# HVP_ADC_CONNECTIONS.net
KiCad netlist of a schematic drawn in Altium Designer
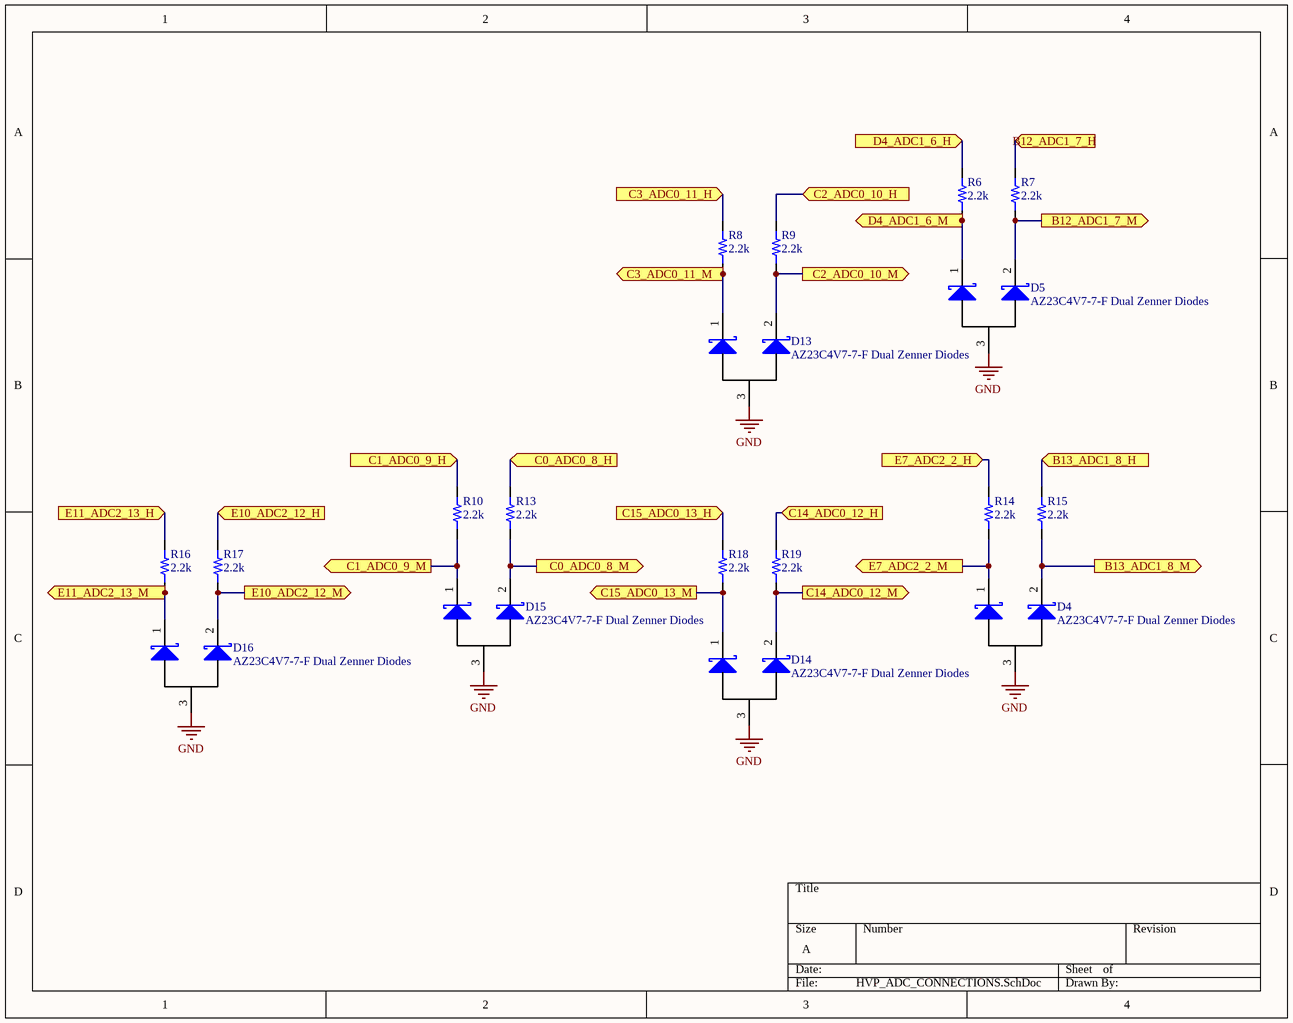
[diagram p0: HVP_ADC_CONNECTIONS.SchDoc]

(export (version "E")
  (design (tool "Eeschema 10.0.6"))
  (components
    (comp (ref "D4")
      (value "AZ23C4V7-7-F Dual Zenner Diodes")
      (footprint "SOT23-3")
      (description "DIODE ZENER ARRAY 4.7V SOT23-3")
      (fields
        (field (name "POWER") "300mW")
        (field (name "MFRPARTNO") "AZ23C4V7-7-F")
        (field (name "CREATED_BY") "Angel Delgado")
      )
      (libsource (lib "Altium-Lib") (part "AZ23C4V7-7-F Dual Zenner Diodes"))
    )
    (comp (ref "D5")
      (value "AZ23C4V7-7-F Dual Zenner Diodes")
      (footprint "SOT23-3")
      (description "DIODE ZENER ARRAY 4.7V SOT23-3")
      (fields
        (field (name "POWER") "300mW")
        (field (name "MFRPARTNO") "AZ23C4V7-7-F")
        (field (name "CREATED_BY") "Angel Delgado")
      )
      (libsource (lib "Altium-Lib") (part "AZ23C4V7-7-F Dual Zenner Diodes"))
    )
    (comp (ref "D13")
      (value "AZ23C4V7-7-F Dual Zenner Diodes")
      (footprint "SOT23-3")
      (description "DIODE ZENER ARRAY 4.7V SOT23-3")
      (fields
        (field (name "POWER") "300mW")
        (field (name "MFRPARTNO") "AZ23C4V7-7-F")
        (field (name "CREATED_BY") "Angel Delgado")
      )
      (libsource (lib "Altium-Lib") (part "AZ23C4V7-7-F Dual Zenner Diodes"))
    )
    (comp (ref "D14")
      (value "AZ23C4V7-7-F Dual Zenner Diodes")
      (footprint "SOT23-3")
      (description "DIODE ZENER ARRAY 4.7V SOT23-3")
      (fields
        (field (name "POWER") "300mW")
        (field (name "MFRPARTNO") "AZ23C4V7-7-F")
        (field (name "CREATED_BY") "Angel Delgado")
      )
      (libsource (lib "Altium-Lib") (part "AZ23C4V7-7-F Dual Zenner Diodes"))
    )
    (comp (ref "D15")
      (value "AZ23C4V7-7-F Dual Zenner Diodes")
      (footprint "SOT23-3")
      (description "DIODE ZENER ARRAY 4.7V SOT23-3")
      (fields
        (field (name "POWER") "300mW")
        (field (name "MFRPARTNO") "AZ23C4V7-7-F")
        (field (name "CREATED_BY") "Angel Delgado")
      )
      (libsource (lib "Altium-Lib") (part "AZ23C4V7-7-F Dual Zenner Diodes"))
    )
    (comp (ref "D16")
      (value "AZ23C4V7-7-F Dual Zenner Diodes")
      (footprint "SOT23-3")
      (description "DIODE ZENER ARRAY 4.7V SOT23-3")
      (fields
        (field (name "POWER") "300mW")
        (field (name "MFRPARTNO") "AZ23C4V7-7-F")
        (field (name "CREATED_BY") "Angel Delgado")
      )
      (libsource (lib "Altium-Lib") (part "AZ23C4V7-7-F Dual Zenner Diodes"))
    )
    (comp (ref "R6")
      (value "2.2k")
      (footprint "RES 0402/1005")
      (fields
        (field (name "TOLERANCE") "1%")
        (field (name "POWER") "1/10W")
        (field (name "Comment") "Resistor 2.2k 0402 1/10W 1%")
        (field (name "CREATED_BY") "Nick Mah")
      )
      (libsource (lib "Altium-Lib") (part "Resistor"))
    )
    (comp (ref "R7")
      (value "2.2k")
      (footprint "RES 0402/1005")
      (fields
        (field (name "TOLERANCE") "1%")
        (field (name "POWER") "1/10W")
        (field (name "Comment") "Resistor 2.2k 0402 1/10W 1%")
        (field (name "CREATED_BY") "Nick Mah")
      )
      (libsource (lib "Altium-Lib") (part "Resistor"))
    )
    (comp (ref "R8")
      (value "2.2k")
      (footprint "RES 0402/1005")
      (fields
        (field (name "TOLERANCE") "1%")
        (field (name "POWER") "1/10W")
        (field (name "Comment") "Resistor 2.2k 0402 1/10W 1%")
        (field (name "CREATED_BY") "Nick Mah")
      )
      (libsource (lib "Altium-Lib") (part "Resistor"))
    )
    (comp (ref "R9")
      (value "2.2k")
      (footprint "RES 0402/1005")
      (fields
        (field (name "TOLERANCE") "1%")
        (field (name "POWER") "1/10W")
        (field (name "Comment") "Resistor 2.2k 0402 1/10W 1%")
        (field (name "CREATED_BY") "Nick Mah")
      )
      (libsource (lib "Altium-Lib") (part "Resistor"))
    )
    (comp (ref "R10")
      (value "2.2k")
      (footprint "RES 0402/1005")
      (fields
        (field (name "TOLERANCE") "1%")
        (field (name "POWER") "1/10W")
        (field (name "Comment") "Resistor 2.2k 0402 1/10W 1%")
        (field (name "CREATED_BY") "Nick Mah")
      )
      (libsource (lib "Altium-Lib") (part "Resistor"))
    )
    (comp (ref "R13")
      (value "2.2k")
      (footprint "RES 0402/1005")
      (fields
        (field (name "TOLERANCE") "1%")
        (field (name "POWER") "1/10W")
        (field (name "Comment") "Resistor 2.2k 0402 1/10W 1%")
        (field (name "CREATED_BY") "Nick Mah")
      )
      (libsource (lib "Altium-Lib") (part "Resistor"))
    )
    (comp (ref "R14")
      (value "2.2k")
      (footprint "RES 0402/1005")
      (fields
        (field (name "TOLERANCE") "1%")
        (field (name "POWER") "1/10W")
        (field (name "Comment") "Resistor 2.2k 0402 1/10W 1%")
        (field (name "CREATED_BY") "Nick Mah")
      )
      (libsource (lib "Altium-Lib") (part "Resistor"))
    )
    (comp (ref "R15")
      (value "2.2k")
      (footprint "RES 0402/1005")
      (fields
        (field (name "TOLERANCE") "1%")
        (field (name "POWER") "1/10W")
        (field (name "Comment") "Resistor 2.2k 0402 1/10W 1%")
        (field (name "CREATED_BY") "Nick Mah")
      )
      (libsource (lib "Altium-Lib") (part "Resistor"))
    )
    (comp (ref "R16")
      (value "2.2k")
      (footprint "RES 0402/1005")
      (fields
        (field (name "TOLERANCE") "1%")
        (field (name "POWER") "1/10W")
        (field (name "Comment") "Resistor 2.2k 0402 1/10W 1%")
        (field (name "CREATED_BY") "Nick Mah")
      )
      (libsource (lib "Altium-Lib") (part "Resistor"))
    )
    (comp (ref "R17")
      (value "2.2k")
      (footprint "RES 0402/1005")
      (fields
        (field (name "TOLERANCE") "1%")
        (field (name "POWER") "1/10W")
        (field (name "Comment") "Resistor 2.2k 0402 1/10W 1%")
        (field (name "CREATED_BY") "Nick Mah")
      )
      (libsource (lib "Altium-Lib") (part "Resistor"))
    )
    (comp (ref "R18")
      (value "2.2k")
      (footprint "RES 0402/1005")
      (fields
        (field (name "TOLERANCE") "1%")
        (field (name "POWER") "1/10W")
        (field (name "Comment") "Resistor 2.2k 0402 1/10W 1%")
        (field (name "CREATED_BY") "Nick Mah")
      )
      (libsource (lib "Altium-Lib") (part "Resistor"))
    )
    (comp (ref "R19")
      (value "2.2k")
      (footprint "RES 0402/1005")
      (fields
        (field (name "TOLERANCE") "1%")
        (field (name "POWER") "1/10W")
        (field (name "Comment") "Resistor 2.2k 0402 1/10W 1%")
        (field (name "CREATED_BY") "Nick Mah")
      )
      (libsource (lib "Altium-Lib") (part "Resistor"))
    )
  )
  (nets
    (net (code "1") (name "/B12_ADC1_7_H") (class "Default")
      (node (ref "R7") (pin "2") (pinfunction "2_2") (pintype "passive"))
    )
    (net (code "2") (name "/B12_ADC1_7_M") (class "Default")
      (node (ref "D5") (pin "2") (pinfunction "2_2") (pintype "passive"))
      (node (ref "R7") (pin "1") (pinfunction "1_1") (pintype "passive"))
    )
    (net (code "3") (name "/B13_ADC1_8_H") (class "Default")
      (node (ref "R15") (pin "2") (pinfunction "2_2") (pintype "passive"))
    )
    (net (code "4") (name "/B13_ADC1_8_M") (class "Default")
      (node (ref "D4") (pin "2") (pinfunction "2_2") (pintype "passive"))
      (node (ref "R15") (pin "1") (pinfunction "1_1") (pintype "passive"))
    )
    (net (code "5") (name "/C0_ADC0_8_H") (class "Default")
      (node (ref "R13") (pin "2") (pinfunction "2_2") (pintype "passive"))
    )
    (net (code "6") (name "/C0_ADC0_8_M") (class "Default")
      (node (ref "D15") (pin "2") (pinfunction "2_2") (pintype "passive"))
      (node (ref "R13") (pin "1") (pinfunction "1_1") (pintype "passive"))
    )
    (net (code "7") (name "/C1_ADC0_9_H") (class "Default")
      (node (ref "R10") (pin "2") (pinfunction "2_2") (pintype "passive"))
    )
    (net (code "8") (name "/C1_ADC0_9_M") (class "Default")
      (node (ref "D15") (pin "1") (pinfunction "1_1") (pintype "passive"))
      (node (ref "R10") (pin "1") (pinfunction "1_1") (pintype "passive"))
    )
    (net (code "9") (name "/C2_ADC0_10_H") (class "Default")
      (node (ref "R9") (pin "2") (pinfunction "2_2") (pintype "passive"))
    )
    (net (code "10") (name "/C2_ADC0_10_M") (class "Default")
      (node (ref "D13") (pin "2") (pinfunction "2_2") (pintype "passive"))
      (node (ref "R9") (pin "1") (pinfunction "1_1") (pintype "passive"))
    )
    (net (code "11") (name "/C3_ADC0_11_H") (class "Default")
      (node (ref "R8") (pin "2") (pinfunction "2_2") (pintype "passive"))
    )
    (net (code "12") (name "/C3_ADC0_11_M") (class "Default")
      (node (ref "D13") (pin "1") (pinfunction "1_1") (pintype "passive"))
      (node (ref "R8") (pin "1") (pinfunction "1_1") (pintype "passive"))
    )
    (net (code "13") (name "/C14_ADC0_12_H") (class "Default")
      (node (ref "R19") (pin "2") (pinfunction "2_2") (pintype "passive"))
    )
    (net (code "14") (name "/C14_ADC0_12_M") (class "Default")
      (node (ref "D14") (pin "2") (pinfunction "2_2") (pintype "passive"))
      (node (ref "R19") (pin "1") (pinfunction "1_1") (pintype "passive"))
    )
    (net (code "15") (name "/C15_ADC0_13_H") (class "Default")
      (node (ref "R18") (pin "2") (pinfunction "2_2") (pintype "passive"))
    )
    (net (code "16") (name "/C15_ADC0_13_M") (class "Default")
      (node (ref "D14") (pin "1") (pinfunction "1_1") (pintype "passive"))
      (node (ref "R18") (pin "1") (pinfunction "1_1") (pintype "passive"))
    )
    (net (code "17") (name "/D4_ADC1_6_H") (class "Default")
      (node (ref "R6") (pin "2") (pinfunction "2_2") (pintype "passive"))
    )
    (net (code "18") (name "/D4_ADC1_6_M") (class "Default")
      (node (ref "D5") (pin "1") (pinfunction "1_1") (pintype "passive"))
      (node (ref "R6") (pin "1") (pinfunction "1_1") (pintype "passive"))
    )
    (net (code "19") (name "/E7_ADC2_2_H") (class "Default")
      (node (ref "R14") (pin "2") (pinfunction "2_2") (pintype "passive"))
    )
    (net (code "20") (name "/E7_ADC2_2_M") (class "Default")
      (node (ref "D4") (pin "1") (pinfunction "1_1") (pintype "passive"))
      (node (ref "R14") (pin "1") (pinfunction "1_1") (pintype "passive"))
    )
    (net (code "21") (name "/E10_ADC2_12_H") (class "Default")
      (node (ref "R17") (pin "2") (pinfunction "2_2") (pintype "passive"))
    )
    (net (code "22") (name "/E10_ADC2_12_M") (class "Default")
      (node (ref "D16") (pin "2") (pinfunction "2_2") (pintype "passive"))
      (node (ref "R17") (pin "1") (pinfunction "1_1") (pintype "passive"))
    )
    (net (code "23") (name "/E11_ADC2_13_H") (class "Default")
      (node (ref "R16") (pin "2") (pinfunction "2_2") (pintype "passive"))
    )
    (net (code "24") (name "/E11_ADC2_13_M") (class "Default")
      (node (ref "D16") (pin "1") (pinfunction "1_1") (pintype "passive"))
      (node (ref "R16") (pin "1") (pinfunction "1_1") (pintype "passive"))
    )
    (net (code "25") (name "GND") (class "Default")
      (node (ref "D13") (pin "3") (pinfunction "3_3") (pintype "passive"))
      (node (ref "D14") (pin "3") (pinfunction "3_3") (pintype "passive"))
      (node (ref "D15") (pin "3") (pinfunction "3_3") (pintype "passive"))
      (node (ref "D16") (pin "3") (pinfunction "3_3") (pintype "passive"))
      (node (ref "D4") (pin "3") (pinfunction "3_3") (pintype "passive"))
      (node (ref "D5") (pin "3") (pinfunction "3_3") (pintype "passive"))
    )
  )
)
